# TapuinoNext-Mini.net
KiCad netlist of a schematic drawn in EAGLE
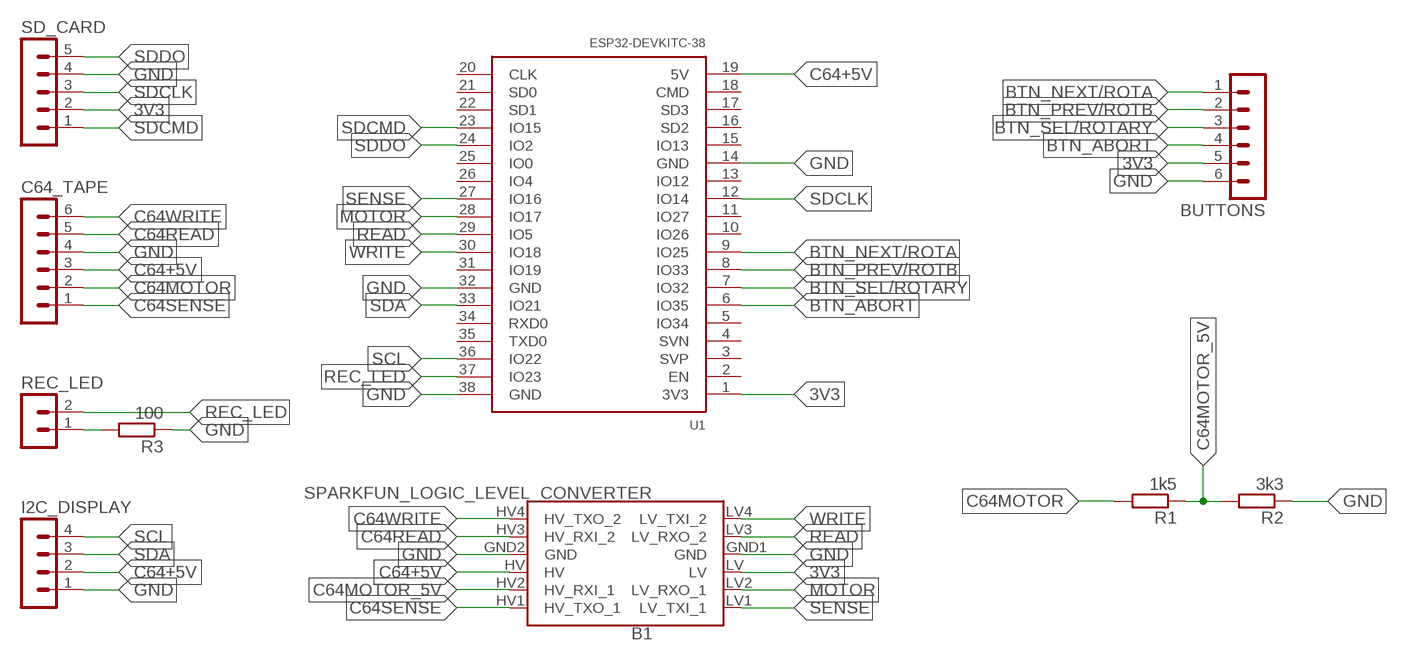
[diagram p0: schematic, sheet 1]

(export (version "E")
  (design (tool "Eeschema 10.0.6"))
  (components
    (comp (ref "B1")
      (value "SPARKFUN_LOGIC_LEVEL_CONVERTER")
      (footprint "eagle-import:SPARKFUN_LOGIC_LEVEL_CONVERTER")
      (libsource (lib "eagle-import") (part "SPARKFUN_LOGIC_LEVEL_CONVERTER"))
    )
    (comp (ref "BUTTONS")
      (value "MA06-1")
      (footprint "eagle-import:MA06-1")
      (libsource (lib "eagle-import") (part "MA06-1"))
    )
    (comp (ref "C64_TAPE")
      (value "MA06-1")
      (footprint "eagle-import:MA06-1")
      (libsource (lib "eagle-import") (part "MA06-1"))
    )
    (comp (ref "I2C_DISPLAY")
      (value "MA04-1")
      (footprint "eagle-import:MA04-1")
      (libsource (lib "eagle-import") (part "MA04-1"))
    )
    (comp (ref "R1")
      (value "1k5")
      (footprint "eagle-import:0207_10")
      (libsource (lib "eagle-import") (part "R-EU_0207/10"))
    )
    (comp (ref "R2")
      (value "3k3")
      (footprint "eagle-import:0207_10")
      (libsource (lib "eagle-import") (part "R-EU_0207/10"))
    )
    (comp (ref "R3")
      (value "100")
      (footprint "eagle-import:0207_10")
      (libsource (lib "eagle-import") (part "R-EU_0207/10"))
    )
    (comp (ref "REC_LED")
      (value "MA02-1")
      (footprint "eagle-import:MA02-1")
      (libsource (lib "eagle-import") (part "MA02-1"))
    )
    (comp (ref "SD_CARD")
      (value "MA05-1")
      (footprint "eagle-import:MA05-1")
      (libsource (lib "eagle-import") (part "MA05-1"))
    )
    (comp (ref "U1")
      (value "ESP32-DEVKITC-38")
      (footprint "eagle-import:ESP32-DEVKITC-38")
      (fields (field (name "AUTHOR") "SWEETLILMRE"))
      (libsource (lib "eagle-import") (part "ESP32-DEVKITC-38"))
    )
  )
  (nets
    (net (code "1") (name "3V3") (class "Default")
      (node (ref "B1") (pin "LV") (pinfunction "LV_LV") (pintype "power_in"))
      (node (ref "BUTTONS") (pin "5") (pinfunction "5_5") (pintype "passive"))
      (node (ref "SD_CARD") (pin "2") (pinfunction "2_2") (pintype "passive"))
      (node (ref "U1") (pin "1") (pinfunction "3V3_1") (pintype "power_in"))
    )
    (net (code "2") (name "BTN_ABORT") (class "Default")
      (node (ref "BUTTONS") (pin "4") (pinfunction "4_4") (pintype "passive"))
      (node (ref "U1") (pin "6") (pinfunction "IO35_6") (pintype "input"))
    )
    (net (code "3") (name "BTN_NEXT{slash}ROTA") (class "Default")
      (node (ref "BUTTONS") (pin "1") (pinfunction "1_1") (pintype "passive"))
      (node (ref "U1") (pin "9") (pinfunction "IO25_9") (pintype "bidirectional"))
    )
    (net (code "4") (name "BTN_PREV{slash}ROTB") (class "Default")
      (node (ref "BUTTONS") (pin "2") (pinfunction "2_2") (pintype "passive"))
      (node (ref "U1") (pin "8") (pinfunction "IO33_8") (pintype "bidirectional"))
    )
    (net (code "5") (name "BTN_SEL{slash}ROTARY") (class "Default")
      (node (ref "BUTTONS") (pin "3") (pinfunction "3_3") (pintype "passive"))
      (node (ref "U1") (pin "7") (pinfunction "IO32_7") (pintype "bidirectional"))
    )
    (net (code "6") (name "C64+5V") (class "Default")
      (node (ref "B1") (pin "HV") (pinfunction "HV_HV") (pintype "power_in"))
      (node (ref "C64_TAPE") (pin "3") (pinfunction "3_3") (pintype "passive"))
      (node (ref "I2C_DISPLAY") (pin "2") (pinfunction "2_2") (pintype "passive"))
      (node (ref "U1") (pin "19") (pinfunction "5V_19") (pintype "power_in"))
    )
    (net (code "7") (name "C64MOTOR") (class "Default")
      (node (ref "C64_TAPE") (pin "2") (pinfunction "2_2") (pintype "passive"))
      (node (ref "R1") (pin "2") (pinfunction "2_2") (pintype "passive"))
    )
    (net (code "8") (name "C64MOTOR_5V") (class "Default")
      (node (ref "B1") (pin "HV2") (pinfunction "HV_RXI_1_HV2") (pintype "bidirectional"))
      (node (ref "R1") (pin "1") (pinfunction "1_1") (pintype "passive"))
      (node (ref "R2") (pin "2") (pinfunction "2_2") (pintype "passive"))
    )
    (net (code "9") (name "C64READ") (class "Default")
      (node (ref "B1") (pin "HV3") (pinfunction "HV_RXI_2_HV3") (pintype "bidirectional"))
      (node (ref "C64_TAPE") (pin "5") (pinfunction "5_5") (pintype "passive"))
    )
    (net (code "10") (name "C64SENSE") (class "Default")
      (node (ref "B1") (pin "HV1") (pinfunction "HV_TXO_1_HV1") (pintype "bidirectional"))
      (node (ref "C64_TAPE") (pin "1") (pinfunction "1_1") (pintype "passive"))
    )
    (net (code "11") (name "C64WRITE") (class "Default")
      (node (ref "B1") (pin "HV4") (pinfunction "HV_TXO_2_HV4") (pintype "bidirectional"))
      (node (ref "C64_TAPE") (pin "6") (pinfunction "6_6") (pintype "passive"))
    )
    (net (code "12") (name "GND") (class "Default")
      (node (ref "B1") (pin "GND1") (pinfunction "GND_GND1") (pintype "power_in"))
      (node (ref "B1") (pin "GND2") (pinfunction "GND_GND2") (pintype "power_in"))
      (node (ref "BUTTONS") (pin "6") (pinfunction "6_6") (pintype "passive"))
      (node (ref "C64_TAPE") (pin "4") (pinfunction "4_4") (pintype "passive"))
      (node (ref "I2C_DISPLAY") (pin "1") (pinfunction "1_1") (pintype "passive"))
      (node (ref "R2") (pin "1") (pinfunction "1_1") (pintype "passive"))
      (node (ref "R3") (pin "1") (pinfunction "1_1") (pintype "passive"))
      (node (ref "SD_CARD") (pin "4") (pinfunction "4_4") (pintype "passive"))
      (node (ref "U1") (pin "14") (pinfunction "GND_14") (pintype "power_in"))
      (node (ref "U1") (pin "32") (pinfunction "GND_32") (pintype "power_in"))
      (node (ref "U1") (pin "38") (pinfunction "GND_38") (pintype "power_in"))
    )
    (net (code "13") (name "MOTOR") (class "Default")
      (node (ref "B1") (pin "LV2") (pinfunction "LV_RXO_1_LV2") (pintype "bidirectional"))
      (node (ref "U1") (pin "28") (pinfunction "IO17_28") (pintype "bidirectional"))
    )
    (net (code "14") (name "Net-(R3-Pad2)") (class "Default")
      (node (ref "R3") (pin "2") (pinfunction "2_2") (pintype "passive"))
      (node (ref "REC_LED") (pin "1") (pinfunction "1_1") (pintype "passive"))
    )
    (net (code "15") (name "READ") (class "Default")
      (node (ref "B1") (pin "LV3") (pinfunction "LV_RXO_2_LV3") (pintype "bidirectional"))
      (node (ref "U1") (pin "29") (pinfunction "IO5_29") (pintype "bidirectional"))
    )
    (net (code "16") (name "REC_LED") (class "Default")
      (node (ref "REC_LED") (pin "2") (pinfunction "2_2") (pintype "passive"))
      (node (ref "U1") (pin "37") (pinfunction "IO23_37") (pintype "bidirectional"))
    )
    (net (code "17") (name "SCL") (class "Default")
      (node (ref "I2C_DISPLAY") (pin "4") (pinfunction "4_4") (pintype "passive"))
      (node (ref "U1") (pin "36") (pinfunction "IO22_36") (pintype "bidirectional"))
    )
    (net (code "18") (name "SDA") (class "Default")
      (node (ref "I2C_DISPLAY") (pin "3") (pinfunction "3_3") (pintype "passive"))
      (node (ref "U1") (pin "33") (pinfunction "IO21_33") (pintype "bidirectional"))
    )
    (net (code "19") (name "SDCLK") (class "Default")
      (node (ref "SD_CARD") (pin "3") (pinfunction "3_3") (pintype "passive"))
      (node (ref "U1") (pin "12") (pinfunction "IO14_12") (pintype "bidirectional"))
    )
    (net (code "20") (name "SDCMD") (class "Default")
      (node (ref "SD_CARD") (pin "1") (pinfunction "1_1") (pintype "passive"))
      (node (ref "U1") (pin "23") (pinfunction "IO15_23") (pintype "bidirectional"))
    )
    (net (code "21") (name "SDDO") (class "Default")
      (node (ref "SD_CARD") (pin "5") (pinfunction "5_5") (pintype "passive"))
      (node (ref "U1") (pin "24") (pinfunction "IO2_24") (pintype "bidirectional"))
    )
    (net (code "22") (name "SENSE") (class "Default")
      (node (ref "B1") (pin "LV1") (pinfunction "LV_TXI_1_LV1") (pintype "bidirectional"))
      (node (ref "U1") (pin "27") (pinfunction "IO16_27") (pintype "bidirectional"))
    )
    (net (code "23") (name "WRITE") (class "Default")
      (node (ref "B1") (pin "LV4") (pinfunction "LV_TXI_2_LV4") (pintype "bidirectional"))
      (node (ref "U1") (pin "30") (pinfunction "IO18_30") (pintype "bidirectional"))
    )
    (net (code "24") (name "unconnected-(U1-CLK-Pad20)") (class "Default")
      (node (ref "U1") (pin "20") (pinfunction "CLK_20") (pintype "bidirectional"))
    )
    (net (code "25") (name "unconnected-(U1-CMD-Pad18)") (class "Default")
      (node (ref "U1") (pin "18") (pinfunction "CMD_18") (pintype "bidirectional"))
    )
    (net (code "26") (name "unconnected-(U1-EN-Pad2)") (class "Default")
      (node (ref "U1") (pin "2") (pinfunction "EN_2") (pintype "bidirectional"))
    )
    (net (code "27") (name "unconnected-(U1-IO0-Pad25)") (class "Default")
      (node (ref "U1") (pin "25") (pinfunction "IO0_25") (pintype "bidirectional"))
    )
    (net (code "28") (name "unconnected-(U1-IO4-Pad26)") (class "Default")
      (node (ref "U1") (pin "26") (pinfunction "IO4_26") (pintype "bidirectional"))
    )
    (net (code "29") (name "unconnected-(U1-IO12-Pad13)") (class "Default")
      (node (ref "U1") (pin "13") (pinfunction "IO12_13") (pintype "bidirectional"))
    )
    (net (code "30") (name "unconnected-(U1-IO13-Pad15)") (class "Default")
      (node (ref "U1") (pin "15") (pinfunction "IO13_15") (pintype "bidirectional"))
    )
    (net (code "31") (name "unconnected-(U1-IO19-Pad31)") (class "Default")
      (node (ref "U1") (pin "31") (pinfunction "IO19_31") (pintype "bidirectional"))
    )
    (net (code "32") (name "unconnected-(U1-IO26-Pad10)") (class "Default")
      (node (ref "U1") (pin "10") (pinfunction "IO26_10") (pintype "bidirectional"))
    )
    (net (code "33") (name "unconnected-(U1-IO27-Pad11)") (class "Default")
      (node (ref "U1") (pin "11") (pinfunction "IO27_11") (pintype "bidirectional"))
    )
    (net (code "34") (name "unconnected-(U1-IO34-Pad5)") (class "Default")
      (node (ref "U1") (pin "5") (pinfunction "IO34_5") (pintype "input"))
    )
    (net (code "35") (name "unconnected-(U1-RXD0-Pad34)") (class "Default")
      (node (ref "U1") (pin "34") (pinfunction "RXD0_34") (pintype "bidirectional"))
    )
    (net (code "36") (name "unconnected-(U1-SD0-Pad21)") (class "Default")
      (node (ref "U1") (pin "21") (pinfunction "SD0_21") (pintype "bidirectional"))
    )
    (net (code "37") (name "unconnected-(U1-SD1-Pad22)") (class "Default")
      (node (ref "U1") (pin "22") (pinfunction "SD1_22") (pintype "bidirectional"))
    )
    (net (code "38") (name "unconnected-(U1-SD2-Pad16)") (class "Default")
      (node (ref "U1") (pin "16") (pinfunction "SD2_16") (pintype "bidirectional"))
    )
    (net (code "39") (name "unconnected-(U1-SD3-Pad17)") (class "Default")
      (node (ref "U1") (pin "17") (pinfunction "SD3_17") (pintype "bidirectional"))
    )
    (net (code "40") (name "unconnected-(U1-SVN-Pad4)") (class "Default")
      (node (ref "U1") (pin "4") (pinfunction "SVN_4") (pintype "input"))
    )
    (net (code "41") (name "unconnected-(U1-SVP-Pad3)") (class "Default")
      (node (ref "U1") (pin "3") (pinfunction "SVP_3") (pintype "input"))
    )
    (net (code "42") (name "unconnected-(U1-TXD0-Pad35)") (class "Default")
      (node (ref "U1") (pin "35") (pinfunction "TXD0_35") (pintype "bidirectional"))
    )
  )
)
